# mcu_shield.net
KiCad netlist of a schematic drawn in Altium Designer
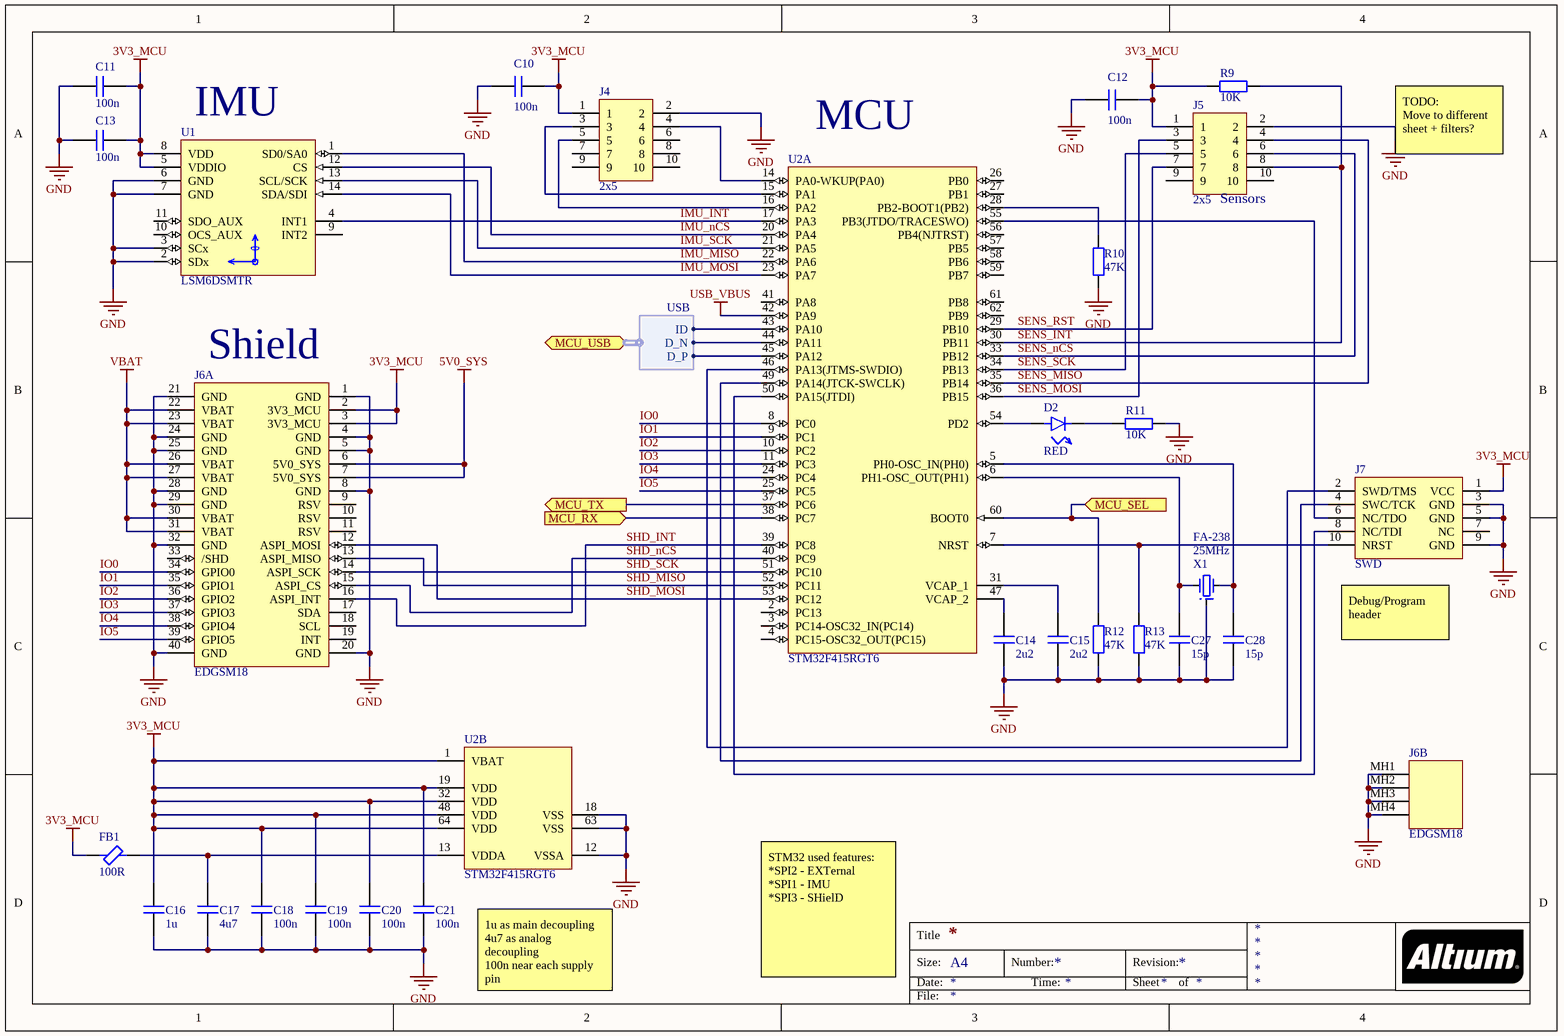
[diagram p0: mcu_shield.SchDoc]

(export (version "E")
  (design (tool "Eeschema 10.0.6"))
  (components
    (comp (ref "C10")
      (value "100n")
      (footprint "CAPC1005X06N")
      (description "Capacitor")
      (fields (field (name "Comment") "cap"))
      (libsource (lib "lib_passives") (part "cap"))
    )
    (comp (ref "C11")
      (value "100n")
      (footprint "CAPC1005X06N")
      (description "Capacitor")
      (fields (field (name "Comment") "cap"))
      (libsource (lib "lib_passives") (part "cap"))
    )
    (comp (ref "C12")
      (value "100n")
      (footprint "CAPC1005X06N")
      (description "Capacitor")
      (fields (field (name "Comment") "cap"))
      (libsource (lib "lib_passives") (part "cap"))
    )
    (comp (ref "C13")
      (value "100n")
      (footprint "CAPC1005X06N")
      (description "Capacitor")
      (fields (field (name "Comment") "cap"))
      (libsource (lib "lib_passives") (part "cap"))
    )
    (comp (ref "C14")
      (value "2u2")
      (footprint "CAPC1608X08N")
      (description "Capacitor")
      (fields (field (name "Comment") "cap"))
      (libsource (lib "lib_passives") (part "cap"))
    )
    (comp (ref "C15")
      (value "2u2")
      (footprint "CAPC1608X08N")
      (description "Capacitor")
      (fields (field (name "Comment") "cap"))
      (libsource (lib "lib_passives") (part "cap"))
    )
    (comp (ref "C16")
      (value "1u")
      (footprint "CAPC1608X08N")
      (description "Capacitor")
      (fields (field (name "Comment") "cap"))
      (libsource (lib "lib_passives") (part "cap"))
    )
    (comp (ref "C17")
      (value "4u7")
      (footprint "CAPC1608X08N")
      (description "Capacitor")
      (fields (field (name "Comment") "cap"))
      (libsource (lib "lib_passives") (part "cap"))
    )
    (comp (ref "C18")
      (value "100n")
      (footprint "CAPC1005X06N")
      (description "Capacitor")
      (fields (field (name "Comment") "cap"))
      (libsource (lib "lib_passives") (part "cap"))
    )
    (comp (ref "C19")
      (value "100n")
      (footprint "CAPC1005X06N")
      (description "Capacitor")
      (fields (field (name "Comment") "cap"))
      (libsource (lib "lib_passives") (part "cap"))
    )
    (comp (ref "C20")
      (value "100n")
      (footprint "CAPC1005X06N")
      (description "Capacitor")
      (fields (field (name "Comment") "cap"))
      (libsource (lib "lib_passives") (part "cap"))
    )
    (comp (ref "C21")
      (value "100n")
      (footprint "CAPC1005X06N")
      (description "Capacitor")
      (fields (field (name "Comment") "cap"))
      (libsource (lib "lib_passives") (part "cap"))
    )
    (comp (ref "C27")
      (value "15p")
      (footprint "CAPC1005X06N")
      (description "Capacitor")
      (fields (field (name "Comment") "cap"))
      (libsource (lib "lib_passives") (part "cap"))
    )
    (comp (ref "C28")
      (value "15p")
      (footprint "CAPC1005X06N")
      (description "Capacitor")
      (fields (field (name "Comment") "cap"))
      (libsource (lib "lib_passives") (part "cap"))
    )
    (comp (ref "D2")
      (value "RED")
      (footprint "CAPCP1005X06N")
      (description "Diode")
      (fields (field (name "Comment") "diode"))
      (libsource (lib "lib_actives") (part "diode"))
    )
    (comp (ref "FB1")
      (value "100R")
      (footprint "INDC1608X08N")
      (description "Inductor")
      (fields (field (name "Comment") "ferrite"))
      (libsource (lib "lib_passives") (part "ferrite"))
    )
    (comp (ref "J4")
      (value "2x5")
      (footprint "hdr_2x5_50mil")
      (description "2x5 Header")
      (libsource (lib "lib_connectors") (part "hdr_2x5"))
    )
    (comp (ref "J5")
      (value "2x5")
      (footprint "hdr_2x5_50mil")
      (description "2x5 Header")
      (libsource (lib "lib_connectors") (part "hdr_2x5"))
    )
    (comp (ref "J6")
      (value "EDGSM18")
      (footprint "edgsm_shield")
      (libsource (lib "") (part "edgsm18_shield_1"))
    )
    (comp (ref "J7")
      (value "SWD")
      (footprint "hdr_2x5_50mil")
      (description "SWD Header")
      (libsource (lib "lib_connectors") (part "hdr_swd"))
    )
    (comp (ref "R9")
      (value "10K")
      (footprint "RESC1005X04N")
      (description "Resistor")
      (fields (field (name "Comment") "res"))
      (libsource (lib "") (part "res_2"))
    )
    (comp (ref "R10")
      (value "47K")
      (footprint "RESC1005X04N")
      (description "Resistor")
      (fields (field (name "Comment") "res"))
      (libsource (lib "lib_passives") (part "res"))
    )
    (comp (ref "R11")
      (value "10K")
      (footprint "RESC1005X04N")
      (description "Resistor")
      (fields (field (name "Comment") "res"))
      (libsource (lib "") (part "res_1"))
    )
    (comp (ref "R12")
      (value "47K")
      (footprint "RESC1005X04N")
      (description "Resistor")
      (fields (field (name "Comment") "res"))
      (libsource (lib "lib_passives") (part "res"))
    )
    (comp (ref "R13")
      (value "47K")
      (footprint "RESC1005X04N")
      (description "Resistor")
      (fields (field (name "Comment") "res"))
      (libsource (lib "lib_passives") (part "res"))
    )
    (comp (ref "U1")
      (value "LSM6DSMTR")
      (footprint "QFN50P300X250X86-14N")
      (description "6DOF IMU acc+gyro")
      (libsource (lib "lib_st") (part "lsm6dsmtr"))
    )
    (comp (ref "U2")
      (value "STM32F415RGT6")
      (footprint "STM-LQFP64_N")
      (fields (field (name "MANUFACTURER") "STMicroelectronics"))
      (libsource (lib "lib_st") (part "STM32F415RGT6"))
    )
    (comp (ref "X1")
      (value "FA-238")
      (footprint "DFN220P320X70-4N")
      (description "Crystal With Shield")
      (fields (field (name "FREQ") "25MHz"))
      (libsource (lib "lib_passives") (part "crystal"))
    )
  )
  (nets
    (net (code "2") (name "/D_N") (class "Default")
      (node (ref "U2") (pin "44") (pinfunction "PA11_44") (pintype "bidirectional"))
    )
    (net (code "3") (name "/D_P") (class "Default")
      (node (ref "U2") (pin "45") (pinfunction "PA12_45") (pintype "bidirectional"))
    )
    (net (code "4") (name "/ID") (class "Default")
      (node (ref "U2") (pin "43") (pinfunction "PA10_43") (pintype "bidirectional"))
    )
    (net (code "5") (name "/IMU_INT") (class "Default")
      (node (ref "U1") (pin "4") (pinfunction "INT1_4") (pintype "open_collector"))
      (node (ref "U2") (pin "17") (pinfunction "PA3_17") (pintype "bidirectional"))
    )
    (net (code "6") (name "/IMU_MISO") (class "Default")
      (node (ref "U1") (pin "1") (pinfunction "SD0/SA0_1") (pintype "bidirectional"))
      (node (ref "U2") (pin "22") (pinfunction "PA6_22") (pintype "bidirectional"))
    )
    (net (code "7") (name "/IMU_MOSI") (class "Default")
      (node (ref "U1") (pin "14") (pinfunction "SDA/SDI_14") (pintype "input"))
      (node (ref "U2") (pin "23") (pinfunction "PA7_23") (pintype "bidirectional"))
    )
    (net (code "8") (name "/IMU_SCK") (class "Default")
      (node (ref "U1") (pin "13") (pinfunction "SCL/SCK_13") (pintype "input"))
      (node (ref "U2") (pin "21") (pinfunction "PA5_21") (pintype "bidirectional"))
    )
    (net (code "9") (name "/IMU_nCS") (class "Default")
      (node (ref "U1") (pin "12") (pinfunction "CS_12") (pintype "input"))
      (node (ref "U2") (pin "20") (pinfunction "PA4_20") (pintype "bidirectional"))
    )
    (net (code "10") (name "/IO0") (class "Default")
      (node (ref "J6") (pin "34") (pinfunction "GPIO0_34") (pintype "bidirectional"))
      (node (ref "U2") (pin "8") (pinfunction "PC0_8") (pintype "bidirectional"))
    )
    (net (code "11") (name "/IO1") (class "Default")
      (node (ref "J6") (pin "35") (pinfunction "GPIO1_35") (pintype "bidirectional"))
      (node (ref "U2") (pin "9") (pinfunction "PC1_9") (pintype "bidirectional"))
    )
    (net (code "12") (name "/IO2") (class "Default")
      (node (ref "J6") (pin "36") (pinfunction "GPIO2_36") (pintype "bidirectional"))
      (node (ref "U2") (pin "10") (pinfunction "PC2_10") (pintype "bidirectional"))
    )
    (net (code "13") (name "/IO3") (class "Default")
      (node (ref "J6") (pin "37") (pinfunction "GPIO3_37") (pintype "bidirectional"))
      (node (ref "U2") (pin "11") (pinfunction "PC3_11") (pintype "bidirectional"))
    )
    (net (code "14") (name "/IO4") (class "Default")
      (node (ref "J6") (pin "38") (pinfunction "GPIO4_38") (pintype "bidirectional"))
      (node (ref "U2") (pin "24") (pinfunction "PC4_24") (pintype "bidirectional"))
    )
    (net (code "15") (name "/IO5") (class "Default")
      (node (ref "J6") (pin "39") (pinfunction "GPIO5_39") (pintype "bidirectional"))
      (node (ref "U2") (pin "25") (pinfunction "PC5_25") (pintype "bidirectional"))
    )
    (net (code "16") (name "/MCU_RX") (class "Default")
      (node (ref "U2") (pin "38") (pinfunction "PC7_38") (pintype "bidirectional"))
    )
    (net (code "17") (name "/MCU_SEL") (class "Default")
      (node (ref "R12") (pin "2") (pinfunction "2_2") (pintype "passive"))
      (node (ref "U2") (pin "60") (pinfunction "BOOT0_60") (pintype "input"))
    )
    (net (code "18") (name "/MCU_TX") (class "Default")
      (node (ref "U2") (pin "37") (pinfunction "PC6_37") (pintype "bidirectional"))
    )
    (net (code "19") (name "/SENS_INT") (class "Default")
      (node (ref "J5") (pin "8") (pinfunction "8_8") (pintype "passive"))
      (node (ref "R9") (pin "1") (pinfunction "1_1") (pintype "passive"))
      (node (ref "U2") (pin "30") (pinfunction "PB11_30") (pintype "bidirectional"))
    )
    (net (code "20") (name "/SENS_MISO") (class "Default")
      (node (ref "J5") (pin "4") (pinfunction "4_4") (pintype "passive"))
      (node (ref "U2") (pin "35") (pinfunction "PB14_35") (pintype "bidirectional"))
    )
    (net (code "21") (name "/SENS_MOSI") (class "Default")
      (node (ref "J5") (pin "3") (pinfunction "3_3") (pintype "passive"))
      (node (ref "U2") (pin "36") (pinfunction "PB15_36") (pintype "bidirectional"))
    )
    (net (code "22") (name "/SENS_RST") (class "Default")
      (node (ref "J5") (pin "7") (pinfunction "7_7") (pintype "passive"))
      (node (ref "U2") (pin "29") (pinfunction "PB10_29") (pintype "bidirectional"))
    )
    (net (code "23") (name "/SENS_SCK") (class "Default")
      (node (ref "J5") (pin "5") (pinfunction "5_5") (pintype "passive"))
      (node (ref "U2") (pin "34") (pinfunction "PB13_34") (pintype "bidirectional"))
    )
    (net (code "24") (name "/SENS_nCS") (class "Default")
      (node (ref "J5") (pin "6") (pinfunction "6_6") (pintype "passive"))
      (node (ref "U2") (pin "33") (pinfunction "PB12_33") (pintype "bidirectional"))
    )
    (net (code "25") (name "/SHD_INT") (class "Default")
      (node (ref "J6") (pin "16") (pinfunction "ASPI_INT_16") (pintype "open_collector"))
      (node (ref "U2") (pin "39") (pinfunction "PC8_39") (pintype "bidirectional"))
    )
    (net (code "26") (name "/SHD_MISO") (class "Default")
      (node (ref "J6") (pin "13") (pinfunction "ASPI_MISO_13") (pintype "bidirectional"))
      (node (ref "U2") (pin "52") (pinfunction "PC11_52") (pintype "bidirectional"))
    )
    (net (code "27") (name "/SHD_MOSI") (class "Default")
      (node (ref "J6") (pin "12") (pinfunction "ASPI_MOSI_12") (pintype "bidirectional"))
      (node (ref "U2") (pin "53") (pinfunction "PC12_53") (pintype "bidirectional"))
    )
    (net (code "28") (name "/SHD_SCK") (class "Default")
      (node (ref "J6") (pin "14") (pinfunction "ASPI_SCK_14") (pintype "bidirectional"))
      (node (ref "U2") (pin "51") (pinfunction "PC10_51") (pintype "bidirectional"))
    )
    (net (code "29") (name "/SHD_nCS") (class "Default")
      (node (ref "J6") (pin "15") (pinfunction "ASPI_CS_15") (pintype "bidirectional"))
      (node (ref "U2") (pin "40") (pinfunction "PC9_40") (pintype "bidirectional"))
    )
    (net (code "31") (name "3V3_MCU") (class "Default")
      (node (ref "C10") (pin "2") (pinfunction "2_2") (pintype "passive"))
      (node (ref "C11") (pin "1") (pinfunction "1_1") (pintype "passive"))
      (node (ref "C12") (pin "2") (pinfunction "2_2") (pintype "passive"))
      (node (ref "C13") (pin "1") (pinfunction "1_1") (pintype "passive"))
      (node (ref "C16") (pin "2") (pinfunction "2_2") (pintype "passive"))
      (node (ref "C18") (pin "2") (pinfunction "2_2") (pintype "passive"))
      (node (ref "C19") (pin "2") (pinfunction "2_2") (pintype "passive"))
      (node (ref "C20") (pin "2") (pinfunction "2_2") (pintype "passive"))
      (node (ref "C21") (pin "2") (pinfunction "2_2") (pintype "passive"))
      (node (ref "FB1") (pin "1") (pinfunction "1_1") (pintype "passive"))
      (node (ref "J4") (pin "1") (pinfunction "1_1") (pintype "passive"))
      (node (ref "J5") (pin "1") (pinfunction "1_1") (pintype "passive"))
      (node (ref "J6") (pin "2") (pinfunction "3V3_MCU_2") (pintype "power_in"))
      (node (ref "J6") (pin "3") (pinfunction "3V3_MCU_3") (pintype "power_in"))
      (node (ref "J7") (pin "1") (pinfunction "VCC_1") (pintype "passive"))
      (node (ref "R9") (pin "2") (pinfunction "2_2") (pintype "passive"))
      (node (ref "U1") (pin "5") (pinfunction "VDDIO_5") (pintype "power_in"))
      (node (ref "U1") (pin "8") (pinfunction "VDD_8") (pintype "power_in"))
      (node (ref "U2") (pin "1") (pinfunction "VBAT_1") (pintype "power_in"))
      (node (ref "U2") (pin "19") (pinfunction "VDD_19") (pintype "power_in"))
      (node (ref "U2") (pin "32") (pinfunction "VDD_32") (pintype "power_in"))
      (node (ref "U2") (pin "48") (pinfunction "VDD_48") (pintype "power_in"))
      (node (ref "U2") (pin "64") (pinfunction "VDD_64") (pintype "power_in"))
    )
    (net (code "32") (name "5V0_SYS") (class "Default")
      (node (ref "J6") (pin "6") (pinfunction "5V0_SYS_6") (pintype "power_in"))
      (node (ref "J6") (pin "7") (pinfunction "5V0_SYS_7") (pintype "power_in"))
    )
    (net (code "33") (name "GND") (class "Default")
      (node (ref "C10") (pin "1") (pinfunction "1_1") (pintype "passive"))
      (node (ref "C11") (pin "2") (pinfunction "2_2") (pintype "passive"))
      (node (ref "C12") (pin "1") (pinfunction "1_1") (pintype "passive"))
      (node (ref "C13") (pin "2") (pinfunction "2_2") (pintype "passive"))
      (node (ref "C14") (pin "1") (pinfunction "1_1") (pintype "passive"))
      (node (ref "C15") (pin "1") (pinfunction "1_1") (pintype "passive"))
      (node (ref "C16") (pin "1") (pinfunction "1_1") (pintype "passive"))
      (node (ref "C17") (pin "1") (pinfunction "1_1") (pintype "passive"))
      (node (ref "C18") (pin "1") (pinfunction "1_1") (pintype "passive"))
      (node (ref "C19") (pin "1") (pinfunction "1_1") (pintype "passive"))
      (node (ref "C20") (pin "1") (pinfunction "1_1") (pintype "passive"))
      (node (ref "C21") (pin "1") (pinfunction "1_1") (pintype "passive"))
      (node (ref "C27") (pin "1") (pinfunction "1_1") (pintype "passive"))
      (node (ref "C28") (pin "1") (pinfunction "1_1") (pintype "passive"))
      (node (ref "J4") (pin "2") (pinfunction "2_2") (pintype "passive"))
      (node (ref "J5") (pin "2") (pinfunction "2_2") (pintype "passive"))
      (node (ref "J6") (pin "1") (pinfunction "GND_1") (pintype "power_in"))
      (node (ref "J6") (pin "20") (pinfunction "GND_20") (pintype "power_in"))
      (node (ref "J6") (pin "21") (pinfunction "GND_21") (pintype "power_in"))
      (node (ref "J6") (pin "24") (pinfunction "GND_24") (pintype "power_in"))
      (node (ref "J6") (pin "25") (pinfunction "GND_25") (pintype "power_in"))
      (node (ref "J6") (pin "28") (pinfunction "GND_28") (pintype "power_in"))
      (node (ref "J6") (pin "29") (pinfunction "GND_29") (pintype "power_in"))
      (node (ref "J6") (pin "32") (pinfunction "GND_32") (pintype "power_in"))
      (node (ref "J6") (pin "4") (pinfunction "GND_4") (pintype "power_in"))
      (node (ref "J6") (pin "40") (pinfunction "GND_40") (pintype "power_in"))
      (node (ref "J6") (pin "5") (pinfunction "GND_5") (pintype "power_in"))
      (node (ref "J6") (pin "8") (pinfunction "GND_8") (pintype "power_in"))
      (node (ref "J6") (pin "MH1") (pinfunction "MH1_MH1") (pintype "passive"))
      (node (ref "J6") (pin "MH2") (pinfunction "MH2_MH2") (pintype "passive"))
      (node (ref "J6") (pin "MH3") (pinfunction "MH3_MH3") (pintype "passive"))
      (node (ref "J6") (pin "MH4") (pinfunction "MH4_MH4") (pintype "passive"))
      (node (ref "J7") (pin "3") (pinfunction "GND_3") (pintype "passive"))
      (node (ref "J7") (pin "5") (pinfunction "GND_5") (pintype "passive"))
      (node (ref "J7") (pin "9") (pinfunction "GND_9") (pintype "passive"))
      (node (ref "R10") (pin "1") (pinfunction "1_1") (pintype "passive"))
      (node (ref "R11") (pin "2") (pinfunction "2_2") (pintype "passive"))
      (node (ref "R12") (pin "1") (pinfunction "1_1") (pintype "passive"))
      (node (ref "R13") (pin "1") (pinfunction "1_1") (pintype "passive"))
      (node (ref "U1") (pin "2") (pinfunction "SDx_2") (pintype "bidirectional"))
      (node (ref "U1") (pin "3") (pinfunction "SCx_3") (pintype "bidirectional"))
      (node (ref "U1") (pin "6") (pinfunction "GND_6") (pintype "power_in"))
      (node (ref "U1") (pin "7") (pinfunction "GND_7") (pintype "power_in"))
      (node (ref "U2") (pin "12") (pinfunction "VSSA_12") (pintype "power_in"))
      (node (ref "U2") (pin "18") (pinfunction "VSS_18") (pintype "power_in"))
      (node (ref "U2") (pin "63") (pinfunction "VSS_63") (pintype "power_in"))
      (node (ref "X1") (pin "SHIELD") (pinfunction "SHIELD_SHIELD") (pintype "passive"))
    )
    (net (code "34") (name "Net-(D2-PadC)") (class "Default")
      (node (ref "D2") (pin "C") (pinfunction "C_C") (pintype "passive"))
      (node (ref "R11") (pin "1") (pinfunction "1_1") (pintype "passive"))
    )
    (net (code "35") (name "Net-(J7-NC{slash}TDI)") (class "Default")
      (node (ref "J7") (pin "8") (pinfunction "NC/TDI_8") (pintype "passive"))
      (node (ref "U2") (pin "50") (pinfunction "PA15(JTDI)_50") (pintype "bidirectional"))
    )
    (net (code "36") (name "Net-(J7-NC{slash}TDO)") (class "Default")
      (node (ref "J7") (pin "6") (pinfunction "NC/TDO_6") (pintype "passive"))
      (node (ref "U2") (pin "55") (pinfunction "PB3(JTDO/TRACESWO)_55") (pintype "bidirectional"))
    )
    (net (code "37") (name "Net-(J7-NRST)") (class "Default")
      (node (ref "J7") (pin "10") (pinfunction "NRST_10") (pintype "passive"))
      (node (ref "R13") (pin "2") (pinfunction "2_2") (pintype "passive"))
      (node (ref "U2") (pin "7") (pinfunction "NRST_7") (pintype "bidirectional"))
    )
    (net (code "38") (name "Net-(J7-SWC{slash}TCK)") (class "Default")
      (node (ref "J7") (pin "4") (pinfunction "SWC/TCK_4") (pintype "passive"))
      (node (ref "U2") (pin "49") (pinfunction "PA14(JTCK-SWCLK)_49") (pintype "bidirectional"))
    )
    (net (code "39") (name "Net-(J7-SWD{slash}TMS)") (class "Default")
      (node (ref "J7") (pin "2") (pinfunction "SWD/TMS_2") (pintype "passive"))
      (node (ref "U2") (pin "46") (pinfunction "PA13(JTMS-SWDIO)_46") (pintype "bidirectional"))
    )
    (net (code "40") (name "Net-(U2A-PA0-WKUP(PA0))") (class "Default")
      (node (ref "J4") (pin "4") (pinfunction "4_4") (pintype "passive"))
      (node (ref "U2") (pin "14") (pinfunction "PA0-WKUP(PA0)_14") (pintype "bidirectional"))
    )
    (net (code "41") (name "Net-(U2A-PA1)") (class "Default")
      (node (ref "J4") (pin "3") (pinfunction "3_3") (pintype "passive"))
      (node (ref "U2") (pin "15") (pinfunction "PA1_15") (pintype "bidirectional"))
    )
    (net (code "42") (name "Net-(U2A-PA2)") (class "Default")
      (node (ref "J4") (pin "5") (pinfunction "5_5") (pintype "passive"))
      (node (ref "U2") (pin "16") (pinfunction "PA2_16") (pintype "bidirectional"))
    )
    (net (code "43") (name "Net-(U2A-PB2-BOOT1(PB2))") (class "Default")
      (node (ref "R10") (pin "2") (pinfunction "2_2") (pintype "passive"))
      (node (ref "U2") (pin "28") (pinfunction "PB2-BOOT1(PB2)_28") (pintype "bidirectional"))
    )
    (net (code "44") (name "Net-(U2A-PD2)") (class "Default")
      (node (ref "D2") (pin "A") (pinfunction "A_A") (pintype "passive"))
      (node (ref "U2") (pin "54") (pinfunction "PD2_54") (pintype "bidirectional"))
    )
    (net (code "45") (name "Net-(U2A-PH0-OSC_IN(PH0))") (class "Default")
      (node (ref "C28") (pin "2") (pinfunction "2_2") (pintype "passive"))
      (node (ref "U2") (pin "5") (pinfunction "PH0-OSC_IN(PH0)_5") (pintype "bidirectional"))
      (node (ref "X1") (pin "2") (pinfunction "2_2") (pintype "passive"))
    )
    (net (code "46") (name "Net-(U2A-PH1-OSC_OUT(PH1))") (class "Default")
      (node (ref "C27") (pin "2") (pinfunction "2_2") (pintype "passive"))
      (node (ref "U2") (pin "6") (pinfunction "PH1-OSC_OUT(PH1)_6") (pintype "bidirectional"))
      (node (ref "X1") (pin "1") (pinfunction "1_1") (pintype "passive"))
    )
    (net (code "47") (name "Net-(U2A-VCAP_1)") (class "Default")
      (node (ref "C15") (pin "2") (pinfunction "2_2") (pintype "passive"))
      (node (ref "U2") (pin "31") (pinfunction "VCAP_1_31") (pintype "power_in"))
    )
    (net (code "48") (name "Net-(U2A-VCAP_2)") (class "Default")
      (node (ref "C14") (pin "2") (pinfunction "2_2") (pintype "passive"))
      (node (ref "U2") (pin "47") (pinfunction "VCAP_2_47") (pintype "power_in"))
    )
    (net (code "49") (name "Net-(U2B-VDDA)") (class "Default")
      (node (ref "C17") (pin "2") (pinfunction "2_2") (pintype "passive"))
      (node (ref "FB1") (pin "2") (pinfunction "2_2") (pintype "passive"))
      (node (ref "U2") (pin "13") (pinfunction "VDDA_13") (pintype "power_in"))
    )
    (net (code "50") (name "USB_VBUS") (class "Default")
      (node (ref "U2") (pin "42") (pinfunction "PA9_42") (pintype "bidirectional"))
    )
    (net (code "51") (name "VBAT") (class "Default")
      (node (ref "J6") (pin "22") (pinfunction "VBAT_22") (pintype "power_in"))
      (node (ref "J6") (pin "23") (pinfunction "VBAT_23") (pintype "power_in"))
      (node (ref "J6") (pin "26") (pinfunction "VBAT_26") (pintype "power_in"))
      (node (ref "J6") (pin "27") (pinfunction "VBAT_27") (pintype "power_in"))
      (node (ref "J6") (pin "30") (pinfunction "VBAT_30") (pintype "power_in"))
      (node (ref "J6") (pin "31") (pinfunction "VBAT_31") (pintype "power_in"))
    )
    (net (code "52") (name "unconnected-(J4-Pad6)") (class "Default")
      (node (ref "J4") (pin "6") (pinfunction "6_6") (pintype "passive"))
    )
    (net (code "53") (name "unconnected-(J4-Pad7)") (class "Default")
      (node (ref "J4") (pin "7") (pinfunction "7_7") (pintype "passive"))
    )
    (net (code "54") (name "unconnected-(J4-Pad8)") (class "Default")
      (node (ref "J4") (pin "8") (pinfunction "8_8") (pintype "passive"))
    )
    (net (code "55") (name "unconnected-(J4-Pad9)") (class "Default")
      (node (ref "J4") (pin "9") (pinfunction "9_9") (pintype "passive"))
    )
    (net (code "56") (name "unconnected-(J4-Pad10)") (class "Default")
      (node (ref "J4") (pin "10") (pinfunction "10_10") (pintype "passive"))
    )
    (net (code "57") (name "unconnected-(J5-Pad9)") (class "Default")
      (node (ref "J5") (pin "9") (pinfunction "9_9") (pintype "passive"))
    )
    (net (code "58") (name "unconnected-(J5-Pad10)") (class "Default")
      (node (ref "J5") (pin "10") (pinfunction "10_10") (pintype "passive"))
    )
    (net (code "59") (name "unconnected-(J6A-INT-Pad19)") (class "Default")
      (node (ref "J6") (pin "19") (pinfunction "INT_19") (pintype "power_in"))
    )
    (net (code "60") (name "unconnected-(J6A-RSV-Pad9)") (class "Default")
      (node (ref "J6") (pin "9") (pinfunction "RSV_9") (pintype "power_in"))
    )
    (net (code "61") (name "unconnected-(J6A-RSV-Pad10)") (class "Default")
      (node (ref "J6") (pin "10") (pinfunction "RSV_10") (pintype "power_in"))
    )
    (net (code "62") (name "unconnected-(J6A-RSV-Pad11)") (class "Default")
      (node (ref "J6") (pin "11") (pinfunction "RSV_11") (pintype "power_in"))
    )
    (net (code "63") (name "unconnected-(J6A-SCL-Pad18)") (class "Default")
      (node (ref "J6") (pin "18") (pinfunction "SCL_18") (pintype "open_collector"))
    )
    (net (code "64") (name "unconnected-(J6A-SDA-Pad17)") (class "Default")
      (node (ref "J6") (pin "17") (pinfunction "SDA_17") (pintype "open_collector"))
    )
    (net (code "65") (name "unconnected-(J6A-{slash}SHD-Pad33)") (class "Default")
      (node (ref "J6") (pin "33") (pinfunction "/SHD_33") (pintype "bidirectional"))
    )
    (net (code "66") (name "unconnected-(J7-NC-Pad7)") (class "Default")
      (node (ref "J7") (pin "7") (pinfunction "NC_7") (pintype "passive"))
    )
    (net (code "67") (name "unconnected-(U1-INT2-Pad9)") (class "Default")
      (node (ref "U1") (pin "9") (pinfunction "INT2_9") (pintype "open_collector"))
    )
    (net (code "68") (name "unconnected-(U1-OCS_AUX-Pad10)") (class "Default")
      (node (ref "U1") (pin "10") (pinfunction "OCS_AUX_10") (pintype "bidirectional"))
    )
    (net (code "69") (name "unconnected-(U1-SDO_AUX-Pad11)") (class "Default")
      (node (ref "U1") (pin "11") (pinfunction "SDO_AUX_11") (pintype "bidirectional"))
    )
    (net (code "70") (name "unconnected-(U2A-PA8-Pad41)") (class "Default")
      (node (ref "U2") (pin "41") (pinfunction "PA8_41") (pintype "bidirectional"))
    )
    (net (code "71") (name "unconnected-(U2A-PB0-Pad26)") (class "Default")
      (node (ref "U2") (pin "26") (pinfunction "PB0_26") (pintype "bidirectional"))
    )
    (net (code "72") (name "unconnected-(U2A-PB1-Pad27)") (class "Default")
      (node (ref "U2") (pin "27") (pinfunction "PB1_27") (pintype "bidirectional"))
    )
    (net (code "73") (name "unconnected-(U2A-PB4(NJTRST)-Pad56)") (class "Default")
      (node (ref "U2") (pin "56") (pinfunction "PB4(NJTRST)_56") (pintype "bidirectional"))
    )
    (net (code "74") (name "unconnected-(U2A-PB5-Pad57)") (class "Default")
      (node (ref "U2") (pin "57") (pinfunction "PB5_57") (pintype "bidirectional"))
    )
    (net (code "75") (name "unconnected-(U2A-PB6-Pad58)") (class "Default")
      (node (ref "U2") (pin "58") (pinfunction "PB6_58") (pintype "bidirectional"))
    )
    (net (code "76") (name "unconnected-(U2A-PB7-Pad59)") (class "Default")
      (node (ref "U2") (pin "59") (pinfunction "PB7_59") (pintype "bidirectional"))
    )
    (net (code "77") (name "unconnected-(U2A-PB8-Pad61)") (class "Default")
      (node (ref "U2") (pin "61") (pinfunction "PB8_61") (pintype "bidirectional"))
    )
    (net (code "78") (name "unconnected-(U2A-PB9-Pad62)") (class "Default")
      (node (ref "U2") (pin "62") (pinfunction "PB9_62") (pintype "bidirectional"))
    )
    (net (code "79") (name "unconnected-(U2A-PC13-Pad2)") (class "Default")
      (node (ref "U2") (pin "2") (pinfunction "PC13_2") (pintype "bidirectional"))
    )
    (net (code "80") (name "unconnected-(U2A-PC14-OSC32_IN(PC14)-Pad3)") (class "Default")
      (node (ref "U2") (pin "3") (pinfunction "PC14-OSC32_IN(PC14)_3") (pintype "bidirectional"))
    )
    (net (code "81") (name "unconnected-(U2A-PC15-OSC32_OUT(PC15)-Pad4)") (class "Default")
      (node (ref "U2") (pin "4") (pinfunction "PC15-OSC32_OUT(PC15)_4") (pintype "bidirectional"))
    )
  )
)
